# gridsEX.net
KiCad netlist of a schematic drawn in EAGLE
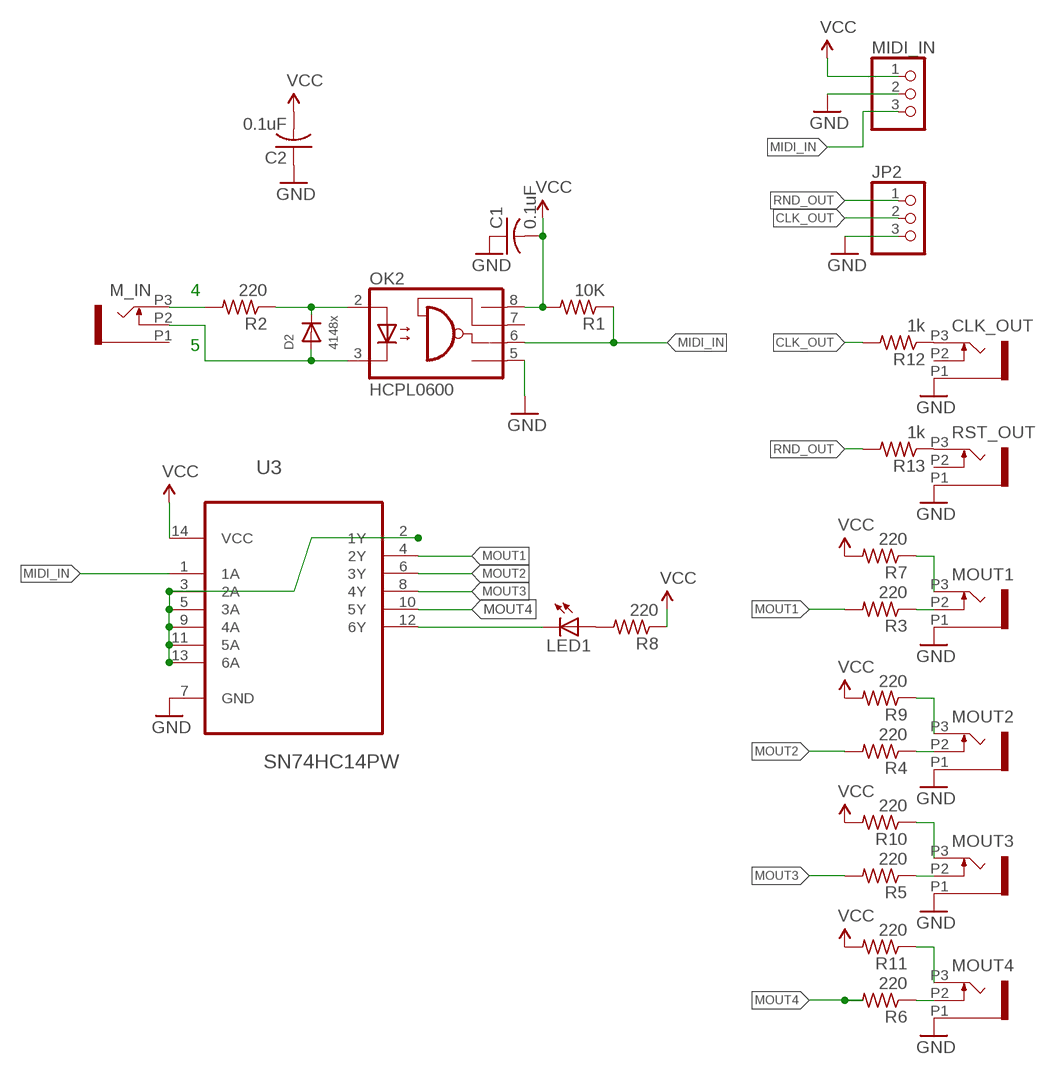
[diagram p0: schematic, sheet 1]

(export (version "E")
  (design (tool "Eeschema 10.0.6"))
  (components
    (comp (ref "C1")
      (value "0.1uF")
      (footprint "eagle-import:RCL_C0603K")
      (libsource (lib "eagle-import") (part "RCL_C-USC0603K"))
    )
    (comp (ref "C2")
      (value "0.1uF")
      (footprint "eagle-import:RCL_C0603K")
      (libsource (lib "eagle-import") (part "RCL_C-USC0603K"))
    )
    (comp (ref "CLK_OUT")
      (value "PJ301_GUI6")
      (footprint "eagle-import:OG-PJ301_VARIATIONS_WQP_PJ_301M6")
      (libsource (lib "eagle-import") (part "PJ301_GUI6"))
    )
    (comp (ref "D2")
      (value "4148x")
      (footprint "eagle-import:SOD-123")
      (libsource (lib "eagle-import") (part "DIODE_SOD-123"))
    )
    (comp (ref "JP2")
      (value "PINHD-1X3")
      (footprint "eagle-import:1X03")
      (libsource (lib "eagle-import") (part "PINHD-1X3"))
    )
    (comp (ref "LED1")
      (value "LED3MM")
      (footprint "eagle-import:LED3MM")
      (libsource (lib "eagle-import") (part "LED3MM"))
    )
    (comp (ref "MIDI_IN")
      (value "PINHD-1X3")
      (footprint "eagle-import:1X03")
      (libsource (lib "eagle-import") (part "PINHD-1X3"))
    )
    (comp (ref "MOUT1")
      (value "PJ301_GUI6")
      (footprint "eagle-import:OG-PJ301_VARIATIONS_WQP_PJ_301M6")
      (libsource (lib "eagle-import") (part "PJ301_GUI6"))
    )
    (comp (ref "MOUT2")
      (value "PJ301_GUI6")
      (footprint "eagle-import:OG-PJ301_VARIATIONS_WQP_PJ_301M6")
      (libsource (lib "eagle-import") (part "PJ301_GUI6"))
    )
    (comp (ref "MOUT3")
      (value "PJ301_GUI6")
      (footprint "eagle-import:OG-PJ301_VARIATIONS_WQP_PJ_301M6")
      (libsource (lib "eagle-import") (part "PJ301_GUI6"))
    )
    (comp (ref "MOUT4")
      (value "PJ301_GUI6")
      (footprint "eagle-import:OG-PJ301_VARIATIONS_WQP_PJ_301M6")
      (libsource (lib "eagle-import") (part "PJ301_GUI6"))
    )
    (comp (ref "M_IN")
      (value "PJ301_GUI6")
      (footprint "eagle-import:OG-PJ301_VARIATIONS_WQP_PJ_301M6")
      (libsource (lib "eagle-import") (part "PJ301_GUI6"))
    )
    (comp (ref "OK2")
      (value "HCPL0600")
      (footprint "eagle-import:SOIC08")
      (libsource (lib "eagle-import") (part "HCPL0600"))
    )
    (comp (ref "R1")
      (value "10K")
      (footprint "eagle-import:RCL_R0603")
      (libsource (lib "eagle-import") (part "RCL_R-US_R0603"))
    )
    (comp (ref "R2")
      (value "220")
      (footprint "eagle-import:RCL_R0603")
      (libsource (lib "eagle-import") (part "RCL_R-US_R0603"))
    )
    (comp (ref "R3")
      (value "220")
      (footprint "eagle-import:RCL_R0603")
      (libsource (lib "eagle-import") (part "RCL_R-US_R0603"))
    )
    (comp (ref "R4")
      (value "220")
      (footprint "eagle-import:RCL_R0603")
      (libsource (lib "eagle-import") (part "RCL_R-US_R0603"))
    )
    (comp (ref "R5")
      (value "220")
      (footprint "eagle-import:RCL_R0603")
      (libsource (lib "eagle-import") (part "RCL_R-US_R0603"))
    )
    (comp (ref "R6")
      (value "220")
      (footprint "eagle-import:RCL_R0603")
      (libsource (lib "eagle-import") (part "RCL_R-US_R0603"))
    )
    (comp (ref "R7")
      (value "220")
      (footprint "eagle-import:RCL_R0603")
      (libsource (lib "eagle-import") (part "RCL_R-US_R0603"))
    )
    (comp (ref "R8")
      (value "220")
      (footprint "eagle-import:RCL_R0603")
      (libsource (lib "eagle-import") (part "RCL_R-US_R0603"))
    )
    (comp (ref "R9")
      (value "220")
      (footprint "eagle-import:RCL_R0603")
      (libsource (lib "eagle-import") (part "RCL_R-US_R0603"))
    )
    (comp (ref "R10")
      (value "220")
      (footprint "eagle-import:RCL_R0603")
      (libsource (lib "eagle-import") (part "RCL_R-US_R0603"))
    )
    (comp (ref "R11")
      (value "220")
      (footprint "eagle-import:RCL_R0603")
      (libsource (lib "eagle-import") (part "RCL_R-US_R0603"))
    )
    (comp (ref "R12")
      (value "1k")
      (footprint "eagle-import:RCL_R0603")
      (libsource (lib "eagle-import") (part "RCL_R-US_R0603"))
    )
    (comp (ref "R13")
      (value "1k")
      (footprint "eagle-import:RCL_R0603")
      (libsource (lib "eagle-import") (part "RCL_R-US_R0603"))
    )
    (comp (ref "RST_OUT")
      (value "PJ301_GUI6")
      (footprint "eagle-import:OG-PJ301_VARIATIONS_WQP_PJ_301M6")
      (libsource (lib "eagle-import") (part "PJ301_GUI6"))
    )
    (comp (ref "U3")
      (value "SN74HC14PW")
      (footprint "eagle-import:SOP65P640X120-14N")
      (libsource (lib "eagle-import") (part "SN74HC14PW"))
    )
  )
  (nets
    (net (code "1") (name "CLK_OUT") (class "Default")
      (node (ref "JP2") (pin "2") (pinfunction "2_2") (pintype "passive"))
      (node (ref "R12") (pin "2") (pinfunction "2_2") (pintype "passive"))
    )
    (net (code "2") (name "GND") (class "Default")
      (node (ref "C1") (pin "1") (pinfunction "1_1") (pintype "passive"))
      (node (ref "C2") (pin "1") (pinfunction "1_1") (pintype "passive"))
      (node (ref "CLK_OUT") (pin "P1") (pinfunction "1_P1") (pintype "passive"))
      (node (ref "JP2") (pin "3") (pinfunction "3_3") (pintype "passive"))
      (node (ref "MIDI_IN") (pin "2") (pinfunction "2_2") (pintype "passive"))
      (node (ref "MOUT1") (pin "P1") (pinfunction "1_P1") (pintype "passive"))
      (node (ref "MOUT2") (pin "P1") (pinfunction "1_P1") (pintype "passive"))
      (node (ref "MOUT3") (pin "P1") (pinfunction "1_P1") (pintype "passive"))
      (node (ref "MOUT4") (pin "P1") (pinfunction "1_P1") (pintype "passive"))
      (node (ref "OK2") (pin "5") (pinfunction "GND_5") (pintype "passive"))
      (node (ref "RST_OUT") (pin "P1") (pinfunction "1_P1") (pintype "passive"))
      (node (ref "U3") (pin "7") (pinfunction "GND_7") (pintype "passive"))
    )
    (net (code "3") (name "MIDI_IN") (class "Default")
      (node (ref "MIDI_IN") (pin "3") (pinfunction "3_3") (pintype "passive"))
      (node (ref "OK2") (pin "6") (pinfunction "VO_6") (pintype "passive"))
      (node (ref "R1") (pin "1") (pinfunction "1_1") (pintype "passive"))
      (node (ref "U3") (pin "1") (pinfunction "1A_1") (pintype "input"))
    )
    (net (code "4") (name "MOUT1") (class "Default")
      (node (ref "R3") (pin "2") (pinfunction "2_2") (pintype "passive"))
      (node (ref "U3") (pin "4") (pinfunction "2Y_4") (pintype "output"))
    )
    (net (code "5") (name "MOUT2") (class "Default")
      (node (ref "R4") (pin "2") (pinfunction "2_2") (pintype "passive"))
      (node (ref "U3") (pin "6") (pinfunction "3Y_6") (pintype "output"))
    )
    (net (code "6") (name "MOUT3") (class "Default")
      (node (ref "R5") (pin "2") (pinfunction "2_2") (pintype "passive"))
      (node (ref "U3") (pin "8") (pinfunction "4Y_8") (pintype "output"))
    )
    (net (code "7") (name "MOUT4") (class "Default")
      (node (ref "R6") (pin "2") (pinfunction "2_2") (pintype "passive"))
      (node (ref "U3") (pin "10") (pinfunction "5Y_10") (pintype "output"))
    )
    (net (code "8") (name "Net-(CLK_OUT-3)") (class "Default")
      (node (ref "CLK_OUT") (pin "P3") (pinfunction "3_P3") (pintype "passive"))
      (node (ref "R12") (pin "1") (pinfunction "1_1") (pintype "passive"))
    )
    (net (code "9") (name "Net-(LED1-C)") (class "Default")
      (node (ref "LED1") (pin "K") (pinfunction "C_K") (pintype "passive"))
      (node (ref "U3") (pin "12") (pinfunction "6Y_12") (pintype "output"))
    )
    (net (code "10") (name "Net-(LED1-PadA)") (class "Default")
      (node (ref "LED1") (pin "A") (pinfunction "A_A") (pintype "passive"))
      (node (ref "R8") (pin "2") (pinfunction "2_2") (pintype "passive"))
    )
    (net (code "11") (name "Net-(MOUT1-2)") (class "Default")
      (node (ref "MOUT1") (pin "P2") (pinfunction "2_P2") (pintype "passive"))
      (node (ref "R3") (pin "1") (pinfunction "1_1") (pintype "passive"))
    )
    (net (code "12") (name "Net-(MOUT1-3)") (class "Default")
      (node (ref "MOUT1") (pin "P3") (pinfunction "3_P3") (pintype "passive"))
      (node (ref "R7") (pin "1") (pinfunction "1_1") (pintype "passive"))
    )
    (net (code "13") (name "Net-(MOUT2-2)") (class "Default")
      (node (ref "MOUT2") (pin "P2") (pinfunction "2_P2") (pintype "passive"))
      (node (ref "R4") (pin "1") (pinfunction "1_1") (pintype "passive"))
    )
    (net (code "14") (name "Net-(MOUT2-3)") (class "Default")
      (node (ref "MOUT2") (pin "P3") (pinfunction "3_P3") (pintype "passive"))
      (node (ref "R9") (pin "1") (pinfunction "1_1") (pintype "passive"))
    )
    (net (code "15") (name "Net-(MOUT3-2)") (class "Default")
      (node (ref "MOUT3") (pin "P2") (pinfunction "2_P2") (pintype "passive"))
      (node (ref "R5") (pin "1") (pinfunction "1_1") (pintype "passive"))
    )
    (net (code "16") (name "Net-(MOUT3-3)") (class "Default")
      (node (ref "MOUT3") (pin "P3") (pinfunction "3_P3") (pintype "passive"))
      (node (ref "R10") (pin "1") (pinfunction "1_1") (pintype "passive"))
    )
    (net (code "17") (name "Net-(MOUT4-2)") (class "Default")
      (node (ref "MOUT4") (pin "P2") (pinfunction "2_P2") (pintype "passive"))
      (node (ref "R6") (pin "1") (pinfunction "1_1") (pintype "passive"))
    )
    (net (code "18") (name "Net-(MOUT4-3)") (class "Default")
      (node (ref "MOUT4") (pin "P3") (pinfunction "3_P3") (pintype "passive"))
      (node (ref "R11") (pin "1") (pinfunction "1_1") (pintype "passive"))
    )
    (net (code "19") (name "Net-(M_IN-2)") (class "Default")
      (node (ref "D2") (pin "A") (pinfunction "A_A") (pintype "passive"))
      (node (ref "M_IN") (pin "P2") (pinfunction "2_P2") (pintype "passive"))
      (node (ref "OK2") (pin "3") (pinfunction "C_3") (pintype "passive"))
    )
    (net (code "20") (name "Net-(M_IN-3)") (class "Default")
      (node (ref "M_IN") (pin "P3") (pinfunction "3_P3") (pintype "passive"))
      (node (ref "R2") (pin "2") (pinfunction "2_2") (pintype "passive"))
    )
    (net (code "21") (name "Net-(OK2-A)") (class "Default")
      (node (ref "D2") (pin "C") (pinfunction "C_C") (pintype "passive"))
      (node (ref "OK2") (pin "2") (pinfunction "A_2") (pintype "passive"))
      (node (ref "R2") (pin "1") (pinfunction "1_1") (pintype "passive"))
    )
    (net (code "22") (name "Net-(RST_OUT-3)") (class "Default")
      (node (ref "R13") (pin "1") (pinfunction "1_1") (pintype "passive"))
      (node (ref "RST_OUT") (pin "P3") (pinfunction "3_P3") (pintype "passive"))
    )
    (net (code "23") (name "Net-(U3-1Y)") (class "Default")
      (node (ref "U3") (pin "11") (pinfunction "5A_11") (pintype "input"))
      (node (ref "U3") (pin "13") (pinfunction "6A_13") (pintype "input"))
      (node (ref "U3") (pin "2") (pinfunction "1Y_2") (pintype "output"))
      (node (ref "U3") (pin "3") (pinfunction "2A_3") (pintype "input"))
      (node (ref "U3") (pin "5") (pinfunction "3A_5") (pintype "input"))
      (node (ref "U3") (pin "9") (pinfunction "4A_9") (pintype "input"))
    )
    (net (code "24") (name "RND_OUT") (class "Default")
      (node (ref "JP2") (pin "1") (pinfunction "1_1") (pintype "passive"))
      (node (ref "R13") (pin "2") (pinfunction "2_2") (pintype "passive"))
    )
    (net (code "25") (name "VCC") (class "Default")
      (node (ref "C1") (pin "2") (pinfunction "2_2") (pintype "passive"))
      (node (ref "C2") (pin "2") (pinfunction "2_2") (pintype "passive"))
      (node (ref "MIDI_IN") (pin "1") (pinfunction "1_1") (pintype "passive"))
      (node (ref "OK2") (pin "8") (pinfunction "VCC_8") (pintype "passive"))
      (node (ref "R1") (pin "2") (pinfunction "2_2") (pintype "passive"))
      (node (ref "R10") (pin "2") (pinfunction "2_2") (pintype "passive"))
      (node (ref "R11") (pin "2") (pinfunction "2_2") (pintype "passive"))
      (node (ref "R7") (pin "2") (pinfunction "2_2") (pintype "passive"))
      (node (ref "R8") (pin "1") (pinfunction "1_1") (pintype "passive"))
      (node (ref "R9") (pin "2") (pinfunction "2_2") (pintype "passive"))
      (node (ref "U3") (pin "14") (pinfunction "VCC_14") (pintype "power_in"))
    )
    (net (code "26") (name "unconnected-(CLK_OUT-2-PadP2)") (class "Default")
      (node (ref "CLK_OUT") (pin "P2") (pinfunction "2_P2") (pintype "passive"))
    )
    (net (code "27") (name "unconnected-(M_IN-1-PadP1)") (class "Default")
      (node (ref "M_IN") (pin "P1") (pinfunction "1_P1") (pintype "passive"))
    )
    (net (code "28") (name "unconnected-(OK2-VE-Pad7)") (class "Default")
      (node (ref "OK2") (pin "7") (pinfunction "VE_7") (pintype "passive"))
    )
    (net (code "29") (name "unconnected-(RST_OUT-2-PadP2)") (class "Default")
      (node (ref "RST_OUT") (pin "P2") (pinfunction "2_P2") (pintype "passive"))
    )
  )
)
